# Connectors.net
KiCad netlist of a schematic drawn in Altium Designer
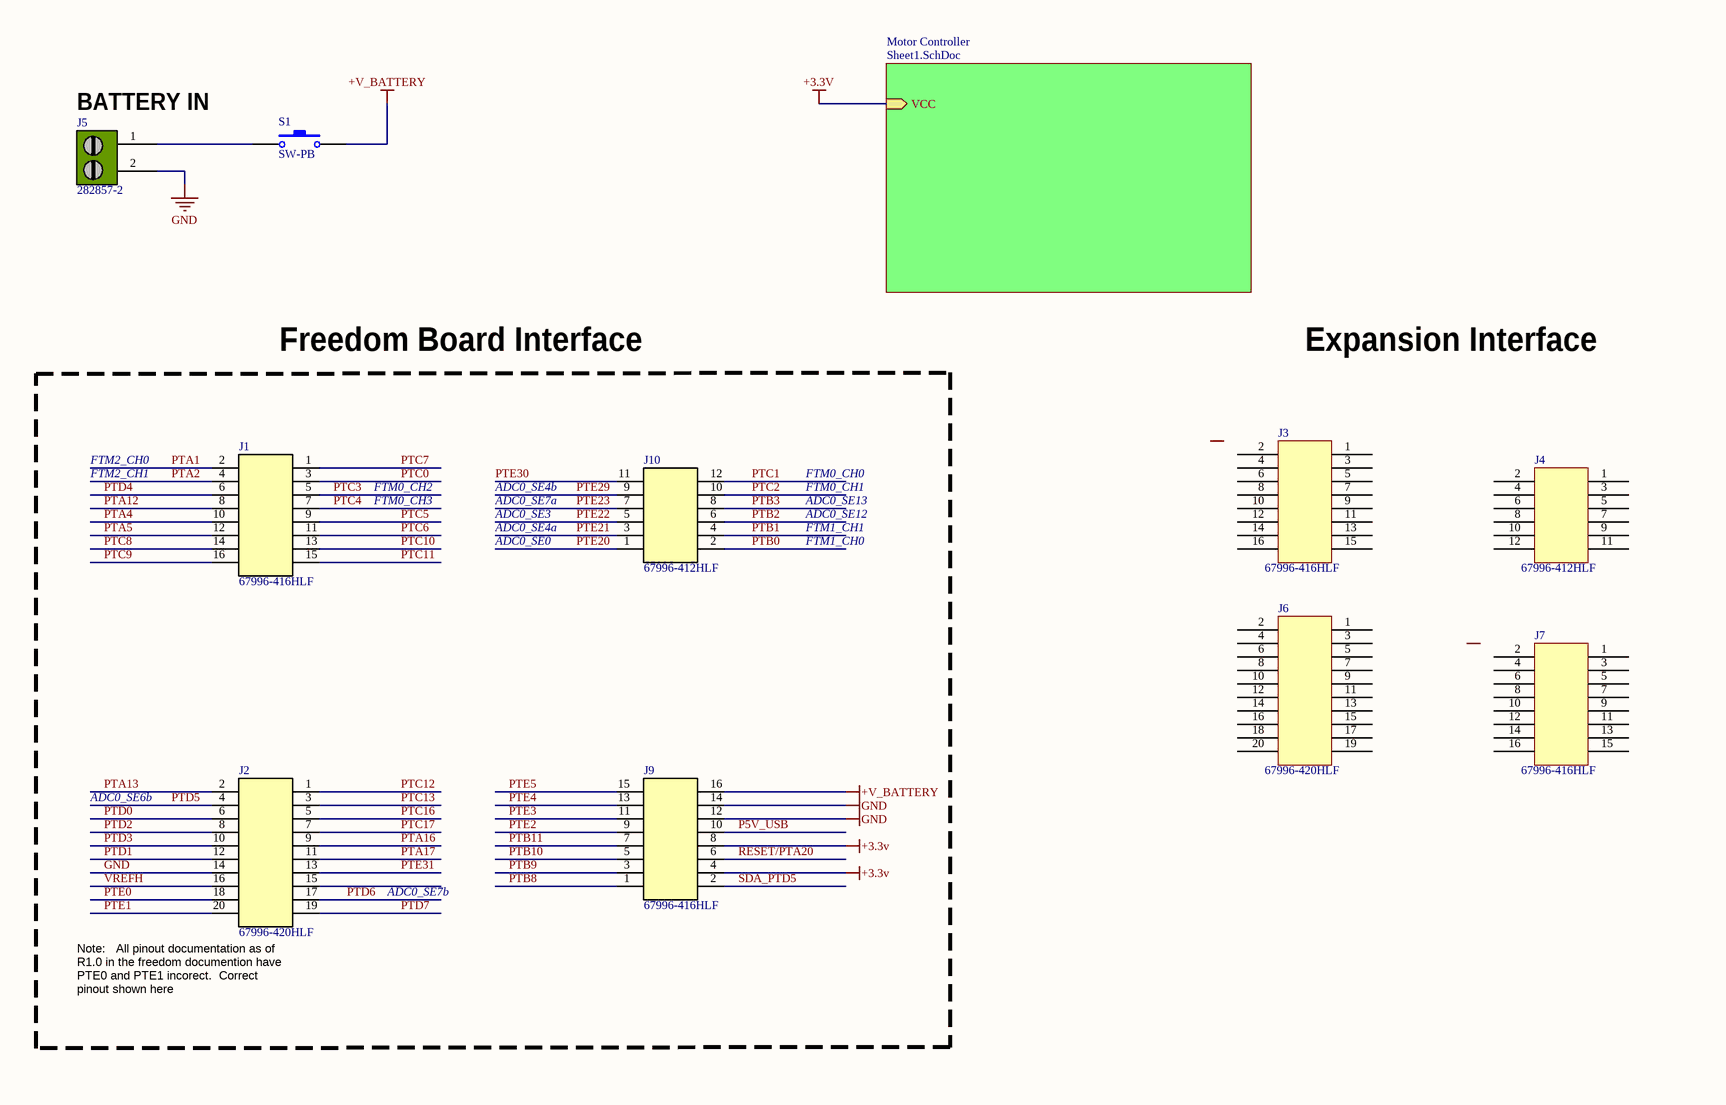
[diagram p0: Connectors.SchDoc, top left]
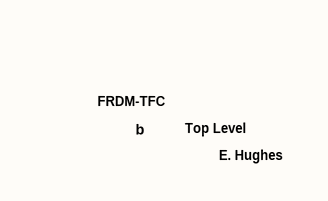
[diagram p1: Connectors.SchDoc, bottom right]

(export (version "E")
  (design (tool "Eeschema 10.0.6"))
  (components
    (comp (ref "J1")
      (value "67996-416HLF")
      (footprint "67996-416HLF")
      (description "CONN HEADER 16POS .100 STR TIN")
      (fields (field (name "MANUFACTURER") "FCI"))
      (libsource (lib "") (part "67996-416HLF_1"))
    )
    (comp (ref "J2")
      (value "67996-420HLF")
      (footprint "67996-420HLF")
      (description "CONN HEADER 20POS .100 STR TIN")
      (fields (field (name "MANUFACTURER") "FCI"))
      (libsource (lib "eConnector") (part "67996-420HLF"))
    )
    (comp (ref "J3")
      (value "67996-416HLF")
      (footprint "67996-416HLF")
      (description "CONN HEADER 16POS .100 STR TIN")
      (libsource (lib "Amphenol_Connectors") (part "67996-416HLF"))
    )
    (comp (ref "J4")
      (value "67996-412HLF")
      (footprint "67996-412HLF")
      (description "CONN HEADER 12POS .100 STR TIN")
      (libsource (lib "Amphenol_Connectors") (part "67996-412HLF"))
    )
    (comp (ref "J5")
      (value "282857-2")
      (footprint "282857-2")
      (description "TERM BLOCK 2POS SIDE ENT 5.08MM")
      (fields (field (name "MANUFACTURER") "TE Connectivity") (field (name "VOLTAGE") "300V"))
      (libsource (lib "eConnector") (part "282857-2"))
    )
    (comp (ref "J6")
      (value "67996-420HLF")
      (footprint "67996-420HLF")
      (description "CONN HEADER 20POS .100 STR TIN")
      (libsource (lib "Amphenol_Connectors") (part "67996-420HLF"))
    )
    (comp (ref "J7")
      (value "67996-416HLF")
      (footprint "67996-416HLF")
      (description "CONN HEADER 16POS .100 STR TIN")
      (libsource (lib "Amphenol_Connectors") (part "67996-416HLF"))
    )
    (comp (ref "J9")
      (value "67996-416HLF")
      (footprint "67996-416HLF")
      (description "CONN HEADER 16POS .100 STR TIN")
      (fields (field (name "MANUFACTURER") "FCI"))
      (libsource (lib "eConnector") (part "67996-416HLF"))
    )
    (comp (ref "J10")
      (value "67996-412HLF")
      (footprint "67996-412HLF")
      (description "CONN HEADER 12POS .100 STR TIN")
      (fields (field (name "MANUFACTURER") "FCI"))
      (libsource (lib "eConnector") (part "67996-412HLF"))
    )
    (comp (ref "S1")
      (value "SW-PB")
      (footprint "SPST")
      (description "Switch")
      (fields (field (name "PUBLISHER") "Altium Limited"))
      (libsource (lib "Miscellaneous Devices") (part "SW-PB"))
    )
  )
  (nets
    (net (code "2") (name "+3.3v") (class "Default")
      (node (ref "J9") (pin "4") (pinfunction "4_4") (pintype "passive"))
      (node (ref "J9") (pin "8") (pinfunction "8_8") (pintype "passive"))
    )
    (net (code "3") (name "+V_BATTERY") (class "Default")
      (node (ref "J9") (pin "16") (pinfunction "16_16") (pintype "passive"))
      (node (ref "S1") (pin "2") (pinfunction "2_2") (pintype "passive"))
    )
    (net (code "4") (name "/P5V_USB") (class "Default")
      (node (ref "J9") (pin "10") (pinfunction "10_10") (pintype "passive"))
    )
    (net (code "5") (name "/PTA1") (class "Default")
      (node (ref "J1") (pin "2") (pinfunction "2_2") (pintype "passive"))
    )
    (net (code "6") (name "/PTA2") (class "Default")
      (node (ref "J1") (pin "4") (pinfunction "4_4") (pintype "passive"))
    )
    (net (code "7") (name "/PTA4") (class "Default")
      (node (ref "J1") (pin "10") (pinfunction "10_10") (pintype "passive"))
    )
    (net (code "8") (name "/PTA5") (class "Default")
      (node (ref "J1") (pin "12") (pinfunction "12_12") (pintype "passive"))
    )
    (net (code "9") (name "/PTA12") (class "Default")
      (node (ref "J1") (pin "8") (pinfunction "8_8") (pintype "passive"))
    )
    (net (code "10") (name "/PTA13") (class "Default")
      (node (ref "J2") (pin "2") (pinfunction "2_2") (pintype "passive"))
    )
    (net (code "11") (name "/PTA16") (class "Default")
      (node (ref "J2") (pin "9") (pinfunction "9_9") (pintype "passive"))
    )
    (net (code "12") (name "/PTA17") (class "Default")
      (node (ref "J2") (pin "11") (pinfunction "11_11") (pintype "passive"))
    )
    (net (code "13") (name "/PTB0") (class "Default")
      (node (ref "J10") (pin "2") (pinfunction "2_2") (pintype "passive"))
    )
    (net (code "14") (name "/PTB1") (class "Default")
      (node (ref "J10") (pin "4") (pinfunction "4_4") (pintype "passive"))
    )
    (net (code "15") (name "/PTB2") (class "Default")
      (node (ref "J10") (pin "6") (pinfunction "6_6") (pintype "passive"))
    )
    (net (code "16") (name "/PTB3") (class "Default")
      (node (ref "J10") (pin "8") (pinfunction "8_8") (pintype "passive"))
    )
    (net (code "17") (name "/PTB8") (class "Default")
      (node (ref "J9") (pin "1") (pinfunction "1_1") (pintype "passive"))
    )
    (net (code "18") (name "/PTB9") (class "Default")
      (node (ref "J9") (pin "3") (pinfunction "3_3") (pintype "passive"))
    )
    (net (code "19") (name "/PTB10") (class "Default")
      (node (ref "J9") (pin "5") (pinfunction "5_5") (pintype "passive"))
    )
    (net (code "20") (name "/PTB11") (class "Default")
      (node (ref "J9") (pin "7") (pinfunction "7_7") (pintype "passive"))
    )
    (net (code "21") (name "/PTC0") (class "Default")
      (node (ref "J1") (pin "3") (pinfunction "3_3") (pintype "passive"))
    )
    (net (code "22") (name "/PTC1") (class "Default")
      (node (ref "J10") (pin "12") (pinfunction "12_12") (pintype "passive"))
    )
    (net (code "23") (name "/PTC2") (class "Default")
      (node (ref "J10") (pin "10") (pinfunction "10_10") (pintype "passive"))
    )
    (net (code "24") (name "/PTC3") (class "Default")
      (node (ref "J1") (pin "5") (pinfunction "5_5") (pintype "passive"))
    )
    (net (code "25") (name "/PTC4") (class "Default")
      (node (ref "J1") (pin "7") (pinfunction "7_7") (pintype "passive"))
    )
    (net (code "26") (name "/PTC5") (class "Default")
      (node (ref "J1") (pin "9") (pinfunction "9_9") (pintype "passive"))
    )
    (net (code "27") (name "/PTC6") (class "Default")
      (node (ref "J1") (pin "11") (pinfunction "11_11") (pintype "passive"))
    )
    (net (code "28") (name "/PTC7") (class "Default")
      (node (ref "J1") (pin "1") (pinfunction "1_1") (pintype "passive"))
    )
    (net (code "29") (name "/PTC8") (class "Default")
      (node (ref "J1") (pin "14") (pinfunction "14_14") (pintype "passive"))
    )
    (net (code "30") (name "/PTC9") (class "Default")
      (node (ref "J1") (pin "16") (pinfunction "16_16") (pintype "passive"))
    )
    (net (code "31") (name "/PTC10") (class "Default")
      (node (ref "J1") (pin "13") (pinfunction "13_13") (pintype "passive"))
    )
    (net (code "32") (name "/PTC11") (class "Default")
      (node (ref "J1") (pin "15") (pinfunction "15_15") (pintype "passive"))
    )
    (net (code "33") (name "/PTC12") (class "Default")
      (node (ref "J2") (pin "1") (pinfunction "1_1") (pintype "passive"))
    )
    (net (code "34") (name "/PTC13") (class "Default")
      (node (ref "J2") (pin "3") (pinfunction "3_3") (pintype "passive"))
    )
    (net (code "35") (name "/PTC16") (class "Default")
      (node (ref "J2") (pin "5") (pinfunction "5_5") (pintype "passive"))
    )
    (net (code "36") (name "/PTC17") (class "Default")
      (node (ref "J2") (pin "7") (pinfunction "7_7") (pintype "passive"))
    )
    (net (code "37") (name "/PTD0") (class "Default")
      (node (ref "J2") (pin "6") (pinfunction "6_6") (pintype "passive"))
    )
    (net (code "38") (name "/PTD1") (class "Default")
      (node (ref "J2") (pin "12") (pinfunction "12_12") (pintype "passive"))
    )
    (net (code "39") (name "/PTD2") (class "Default")
      (node (ref "J2") (pin "8") (pinfunction "8_8") (pintype "passive"))
    )
    (net (code "40") (name "/PTD3") (class "Default")
      (node (ref "J2") (pin "10") (pinfunction "10_10") (pintype "passive"))
    )
    (net (code "41") (name "/PTD4") (class "Default")
      (node (ref "J1") (pin "6") (pinfunction "6_6") (pintype "passive"))
    )
    (net (code "42") (name "/PTD5") (class "Default")
      (node (ref "J2") (pin "4") (pinfunction "4_4") (pintype "passive"))
    )
    (net (code "43") (name "/PTD6") (class "Default")
      (node (ref "J2") (pin "17") (pinfunction "17_17") (pintype "passive"))
    )
    (net (code "44") (name "/PTD7") (class "Default")
      (node (ref "J2") (pin "19") (pinfunction "19_19") (pintype "passive"))
    )
    (net (code "45") (name "/PTE0") (class "Default")
      (node (ref "J2") (pin "18") (pinfunction "18_18") (pintype "passive"))
    )
    (net (code "46") (name "/PTE1") (class "Default")
      (node (ref "J2") (pin "20") (pinfunction "20_20") (pintype "passive"))
    )
    (net (code "47") (name "/PTE2") (class "Default")
      (node (ref "J9") (pin "9") (pinfunction "9_9") (pintype "passive"))
    )
    (net (code "48") (name "/PTE3") (class "Default")
      (node (ref "J9") (pin "11") (pinfunction "11_11") (pintype "passive"))
    )
    (net (code "49") (name "/PTE4") (class "Default")
      (node (ref "J9") (pin "13") (pinfunction "13_13") (pintype "passive"))
    )
    (net (code "50") (name "/PTE5") (class "Default")
      (node (ref "J9") (pin "15") (pinfunction "15_15") (pintype "passive"))
    )
    (net (code "51") (name "/PTE20") (class "Default")
      (node (ref "J10") (pin "1") (pinfunction "1_1") (pintype "passive"))
    )
    (net (code "52") (name "/PTE21") (class "Default")
      (node (ref "J10") (pin "3") (pinfunction "3_3") (pintype "passive"))
    )
    (net (code "53") (name "/PTE22") (class "Default")
      (node (ref "J10") (pin "5") (pinfunction "5_5") (pintype "passive"))
    )
    (net (code "54") (name "/PTE23") (class "Default")
      (node (ref "J10") (pin "7") (pinfunction "7_7") (pintype "passive"))
    )
    (net (code "55") (name "/PTE29") (class "Default")
      (node (ref "J10") (pin "9") (pinfunction "9_9") (pintype "passive"))
    )
    (net (code "56") (name "/PTE30") (class "Default")
      (node (ref "J10") (pin "11") (pinfunction "11_11") (pintype "passive"))
    )
    (net (code "57") (name "/PTE31") (class "Default")
      (node (ref "J2") (pin "13") (pinfunction "13_13") (pintype "passive"))
    )
    (net (code "58") (name "/RESET{slash}PTA20") (class "Default")
      (node (ref "J9") (pin "6") (pinfunction "6_6") (pintype "passive"))
    )
    (net (code "59") (name "/SDA_PTD5") (class "Default")
      (node (ref "J9") (pin "2") (pinfunction "2_2") (pintype "passive"))
    )
    (net (code "60") (name "/VREFH") (class "Default")
      (node (ref "J2") (pin "16") (pinfunction "16_16") (pintype "passive"))
    )
    (net (code "61") (name "GND") (class "Default")
      (node (ref "J2") (pin "14") (pinfunction "14_14") (pintype "passive"))
      (node (ref "J5") (pin "2") (pinfunction "2_2") (pintype "passive"))
      (node (ref "J9") (pin "12") (pinfunction "12_12") (pintype "passive"))
      (node (ref "J9") (pin "14") (pinfunction "14_14") (pintype "passive"))
    )
    (net (code "62") (name "Net-(J5-Pad1)") (class "Default")
      (node (ref "J5") (pin "1") (pinfunction "1_1") (pintype "passive"))
      (node (ref "S1") (pin "1") (pinfunction "1_1") (pintype "passive"))
    )
    (net (code "63") (name "unconnected-(J2-Pad15)") (class "Default")
      (node (ref "J2") (pin "15") (pinfunction "15_15") (pintype "passive"))
    )
    (net (code "64") (name "unconnected-(J3-Pad1)") (class "Default")
      (node (ref "J3") (pin "1") (pinfunction "1_1") (pintype "passive"))
    )
    (net (code "65") (name "unconnected-(J3-Pad2)") (class "Default")
      (node (ref "J3") (pin "2") (pinfunction "2_2") (pintype "passive"))
    )
    (net (code "66") (name "unconnected-(J3-Pad3)") (class "Default")
      (node (ref "J3") (pin "3") (pinfunction "3_3") (pintype "passive"))
    )
    (net (code "67") (name "unconnected-(J3-Pad4)") (class "Default")
      (node (ref "J3") (pin "4") (pinfunction "4_4") (pintype "passive"))
    )
    (net (code "68") (name "unconnected-(J3-Pad5)") (class "Default")
      (node (ref "J3") (pin "5") (pinfunction "5_5") (pintype "passive"))
    )
    (net (code "69") (name "unconnected-(J3-Pad6)") (class "Default")
      (node (ref "J3") (pin "6") (pinfunction "6_6") (pintype "passive"))
    )
    (net (code "70") (name "unconnected-(J3-Pad7)") (class "Default")
      (node (ref "J3") (pin "7") (pinfunction "7_7") (pintype "passive"))
    )
    (net (code "71") (name "unconnected-(J3-Pad8)") (class "Default")
      (node (ref "J3") (pin "8") (pinfunction "8_8") (pintype "passive"))
    )
    (net (code "72") (name "unconnected-(J3-Pad9)") (class "Default")
      (node (ref "J3") (pin "9") (pinfunction "9_9") (pintype "passive"))
    )
    (net (code "73") (name "unconnected-(J3-Pad10)") (class "Default")
      (node (ref "J3") (pin "10") (pinfunction "10_10") (pintype "passive"))
    )
    (net (code "74") (name "unconnected-(J3-Pad11)") (class "Default")
      (node (ref "J3") (pin "11") (pinfunction "11_11") (pintype "passive"))
    )
    (net (code "75") (name "unconnected-(J3-Pad12)") (class "Default")
      (node (ref "J3") (pin "12") (pinfunction "12_12") (pintype "passive"))
    )
    (net (code "76") (name "unconnected-(J3-Pad13)") (class "Default")
      (node (ref "J3") (pin "13") (pinfunction "13_13") (pintype "passive"))
    )
    (net (code "77") (name "unconnected-(J3-Pad14)") (class "Default")
      (node (ref "J3") (pin "14") (pinfunction "14_14") (pintype "passive"))
    )
    (net (code "78") (name "unconnected-(J3-Pad15)") (class "Default")
      (node (ref "J3") (pin "15") (pinfunction "15_15") (pintype "passive"))
    )
    (net (code "79") (name "unconnected-(J3-Pad16)") (class "Default")
      (node (ref "J3") (pin "16") (pinfunction "16_16") (pintype "passive"))
    )
    (net (code "80") (name "unconnected-(J4-Pad1)") (class "Default")
      (node (ref "J4") (pin "1") (pinfunction "1_1") (pintype "passive"))
    )
    (net (code "81") (name "unconnected-(J4-Pad2)") (class "Default")
      (node (ref "J4") (pin "2") (pinfunction "2_2") (pintype "passive"))
    )
    (net (code "82") (name "unconnected-(J4-Pad3)") (class "Default")
      (node (ref "J4") (pin "3") (pinfunction "3_3") (pintype "passive"))
    )
    (net (code "83") (name "unconnected-(J4-Pad4)") (class "Default")
      (node (ref "J4") (pin "4") (pinfunction "4_4") (pintype "passive"))
    )
    (net (code "84") (name "unconnected-(J4-Pad5)") (class "Default")
      (node (ref "J4") (pin "5") (pinfunction "5_5") (pintype "passive"))
    )
    (net (code "85") (name "unconnected-(J4-Pad6)") (class "Default")
      (node (ref "J4") (pin "6") (pinfunction "6_6") (pintype "passive"))
    )
    (net (code "86") (name "unconnected-(J4-Pad7)") (class "Default")
      (node (ref "J4") (pin "7") (pinfunction "7_7") (pintype "passive"))
    )
    (net (code "87") (name "unconnected-(J4-Pad8)") (class "Default")
      (node (ref "J4") (pin "8") (pinfunction "8_8") (pintype "passive"))
    )
    (net (code "88") (name "unconnected-(J4-Pad9)") (class "Default")
      (node (ref "J4") (pin "9") (pinfunction "9_9") (pintype "passive"))
    )
    (net (code "89") (name "unconnected-(J4-Pad10)") (class "Default")
      (node (ref "J4") (pin "10") (pinfunction "10_10") (pintype "passive"))
    )
    (net (code "90") (name "unconnected-(J4-Pad11)") (class "Default")
      (node (ref "J4") (pin "11") (pinfunction "11_11") (pintype "passive"))
    )
    (net (code "91") (name "unconnected-(J4-Pad12)") (class "Default")
      (node (ref "J4") (pin "12") (pinfunction "12_12") (pintype "passive"))
    )
    (net (code "92") (name "unconnected-(J6-Pad1)") (class "Default")
      (node (ref "J6") (pin "1") (pinfunction "1_1") (pintype "passive"))
    )
    (net (code "93") (name "unconnected-(J6-Pad2)") (class "Default")
      (node (ref "J6") (pin "2") (pinfunction "2_2") (pintype "passive"))
    )
    (net (code "94") (name "unconnected-(J6-Pad3)") (class "Default")
      (node (ref "J6") (pin "3") (pinfunction "3_3") (pintype "passive"))
    )
    (net (code "95") (name "unconnected-(J6-Pad4)") (class "Default")
      (node (ref "J6") (pin "4") (pinfunction "4_4") (pintype "passive"))
    )
    (net (code "96") (name "unconnected-(J6-Pad5)") (class "Default")
      (node (ref "J6") (pin "5") (pinfunction "5_5") (pintype "passive"))
    )
    (net (code "97") (name "unconnected-(J6-Pad6)") (class "Default")
      (node (ref "J6") (pin "6") (pinfunction "6_6") (pintype "passive"))
    )
    (net (code "98") (name "unconnected-(J6-Pad7)") (class "Default")
      (node (ref "J6") (pin "7") (pinfunction "7_7") (pintype "passive"))
    )
    (net (code "99") (name "unconnected-(J6-Pad8)") (class "Default")
      (node (ref "J6") (pin "8") (pinfunction "8_8") (pintype "passive"))
    )
    (net (code "100") (name "unconnected-(J6-Pad9)") (class "Default")
      (node (ref "J6") (pin "9") (pinfunction "9_9") (pintype "passive"))
    )
    (net (code "101") (name "unconnected-(J6-Pad10)") (class "Default")
      (node (ref "J6") (pin "10") (pinfunction "10_10") (pintype "passive"))
    )
    (net (code "102") (name "unconnected-(J6-Pad11)") (class "Default")
      (node (ref "J6") (pin "11") (pinfunction "11_11") (pintype "passive"))
    )
    (net (code "103") (name "unconnected-(J6-Pad12)") (class "Default")
      (node (ref "J6") (pin "12") (pinfunction "12_12") (pintype "passive"))
    )
    (net (code "104") (name "unconnected-(J6-Pad13)") (class "Default")
      (node (ref "J6") (pin "13") (pinfunction "13_13") (pintype "passive"))
    )
    (net (code "105") (name "unconnected-(J6-Pad14)") (class "Default")
      (node (ref "J6") (pin "14") (pinfunction "14_14") (pintype "passive"))
    )
    (net (code "106") (name "unconnected-(J6-Pad15)") (class "Default")
      (node (ref "J6") (pin "15") (pinfunction "15_15") (pintype "passive"))
    )
    (net (code "107") (name "unconnected-(J6-Pad16)") (class "Default")
      (node (ref "J6") (pin "16") (pinfunction "16_16") (pintype "passive"))
    )
    (net (code "108") (name "unconnected-(J6-Pad17)") (class "Default")
      (node (ref "J6") (pin "17") (pinfunction "17_17") (pintype "passive"))
    )
    (net (code "109") (name "unconnected-(J6-Pad18)") (class "Default")
      (node (ref "J6") (pin "18") (pinfunction "18_18") (pintype "passive"))
    )
    (net (code "110") (name "unconnected-(J6-Pad19)") (class "Default")
      (node (ref "J6") (pin "19") (pinfunction "19_19") (pintype "passive"))
    )
    (net (code "111") (name "unconnected-(J6-Pad20)") (class "Default")
      (node (ref "J6") (pin "20") (pinfunction "20_20") (pintype "passive"))
    )
    (net (code "112") (name "unconnected-(J7-Pad1)") (class "Default")
      (node (ref "J7") (pin "1") (pinfunction "1_1") (pintype "passive"))
    )
    (net (code "113") (name "unconnected-(J7-Pad2)") (class "Default")
      (node (ref "J7") (pin "2") (pinfunction "2_2") (pintype "passive"))
    )
    (net (code "114") (name "unconnected-(J7-Pad3)") (class "Default")
      (node (ref "J7") (pin "3") (pinfunction "3_3") (pintype "passive"))
    )
    (net (code "115") (name "unconnected-(J7-Pad4)") (class "Default")
      (node (ref "J7") (pin "4") (pinfunction "4_4") (pintype "passive"))
    )
    (net (code "116") (name "unconnected-(J7-Pad5)") (class "Default")
      (node (ref "J7") (pin "5") (pinfunction "5_5") (pintype "passive"))
    )
    (net (code "117") (name "unconnected-(J7-Pad6)") (class "Default")
      (node (ref "J7") (pin "6") (pinfunction "6_6") (pintype "passive"))
    )
    (net (code "118") (name "unconnected-(J7-Pad7)") (class "Default")
      (node (ref "J7") (pin "7") (pinfunction "7_7") (pintype "passive"))
    )
    (net (code "119") (name "unconnected-(J7-Pad8)") (class "Default")
      (node (ref "J7") (pin "8") (pinfunction "8_8") (pintype "passive"))
    )
    (net (code "120") (name "unconnected-(J7-Pad9)") (class "Default")
      (node (ref "J7") (pin "9") (pinfunction "9_9") (pintype "passive"))
    )
    (net (code "121") (name "unconnected-(J7-Pad10)") (class "Default")
      (node (ref "J7") (pin "10") (pinfunction "10_10") (pintype "passive"))
    )
    (net (code "122") (name "unconnected-(J7-Pad11)") (class "Default")
      (node (ref "J7") (pin "11") (pinfunction "11_11") (pintype "passive"))
    )
    (net (code "123") (name "unconnected-(J7-Pad12)") (class "Default")
      (node (ref "J7") (pin "12") (pinfunction "12_12") (pintype "passive"))
    )
    (net (code "124") (name "unconnected-(J7-Pad13)") (class "Default")
      (node (ref "J7") (pin "13") (pinfunction "13_13") (pintype "passive"))
    )
    (net (code "125") (name "unconnected-(J7-Pad14)") (class "Default")
      (node (ref "J7") (pin "14") (pinfunction "14_14") (pintype "passive"))
    )
    (net (code "126") (name "unconnected-(J7-Pad15)") (class "Default")
      (node (ref "J7") (pin "15") (pinfunction "15_15") (pintype "passive"))
    )
    (net (code "127") (name "unconnected-(J7-Pad16)") (class "Default")
      (node (ref "J7") (pin "16") (pinfunction "16_16") (pintype "passive"))
    )
  )
)
